# Central_Board.net
KiCad netlist of a schematic drawn in EAGLE
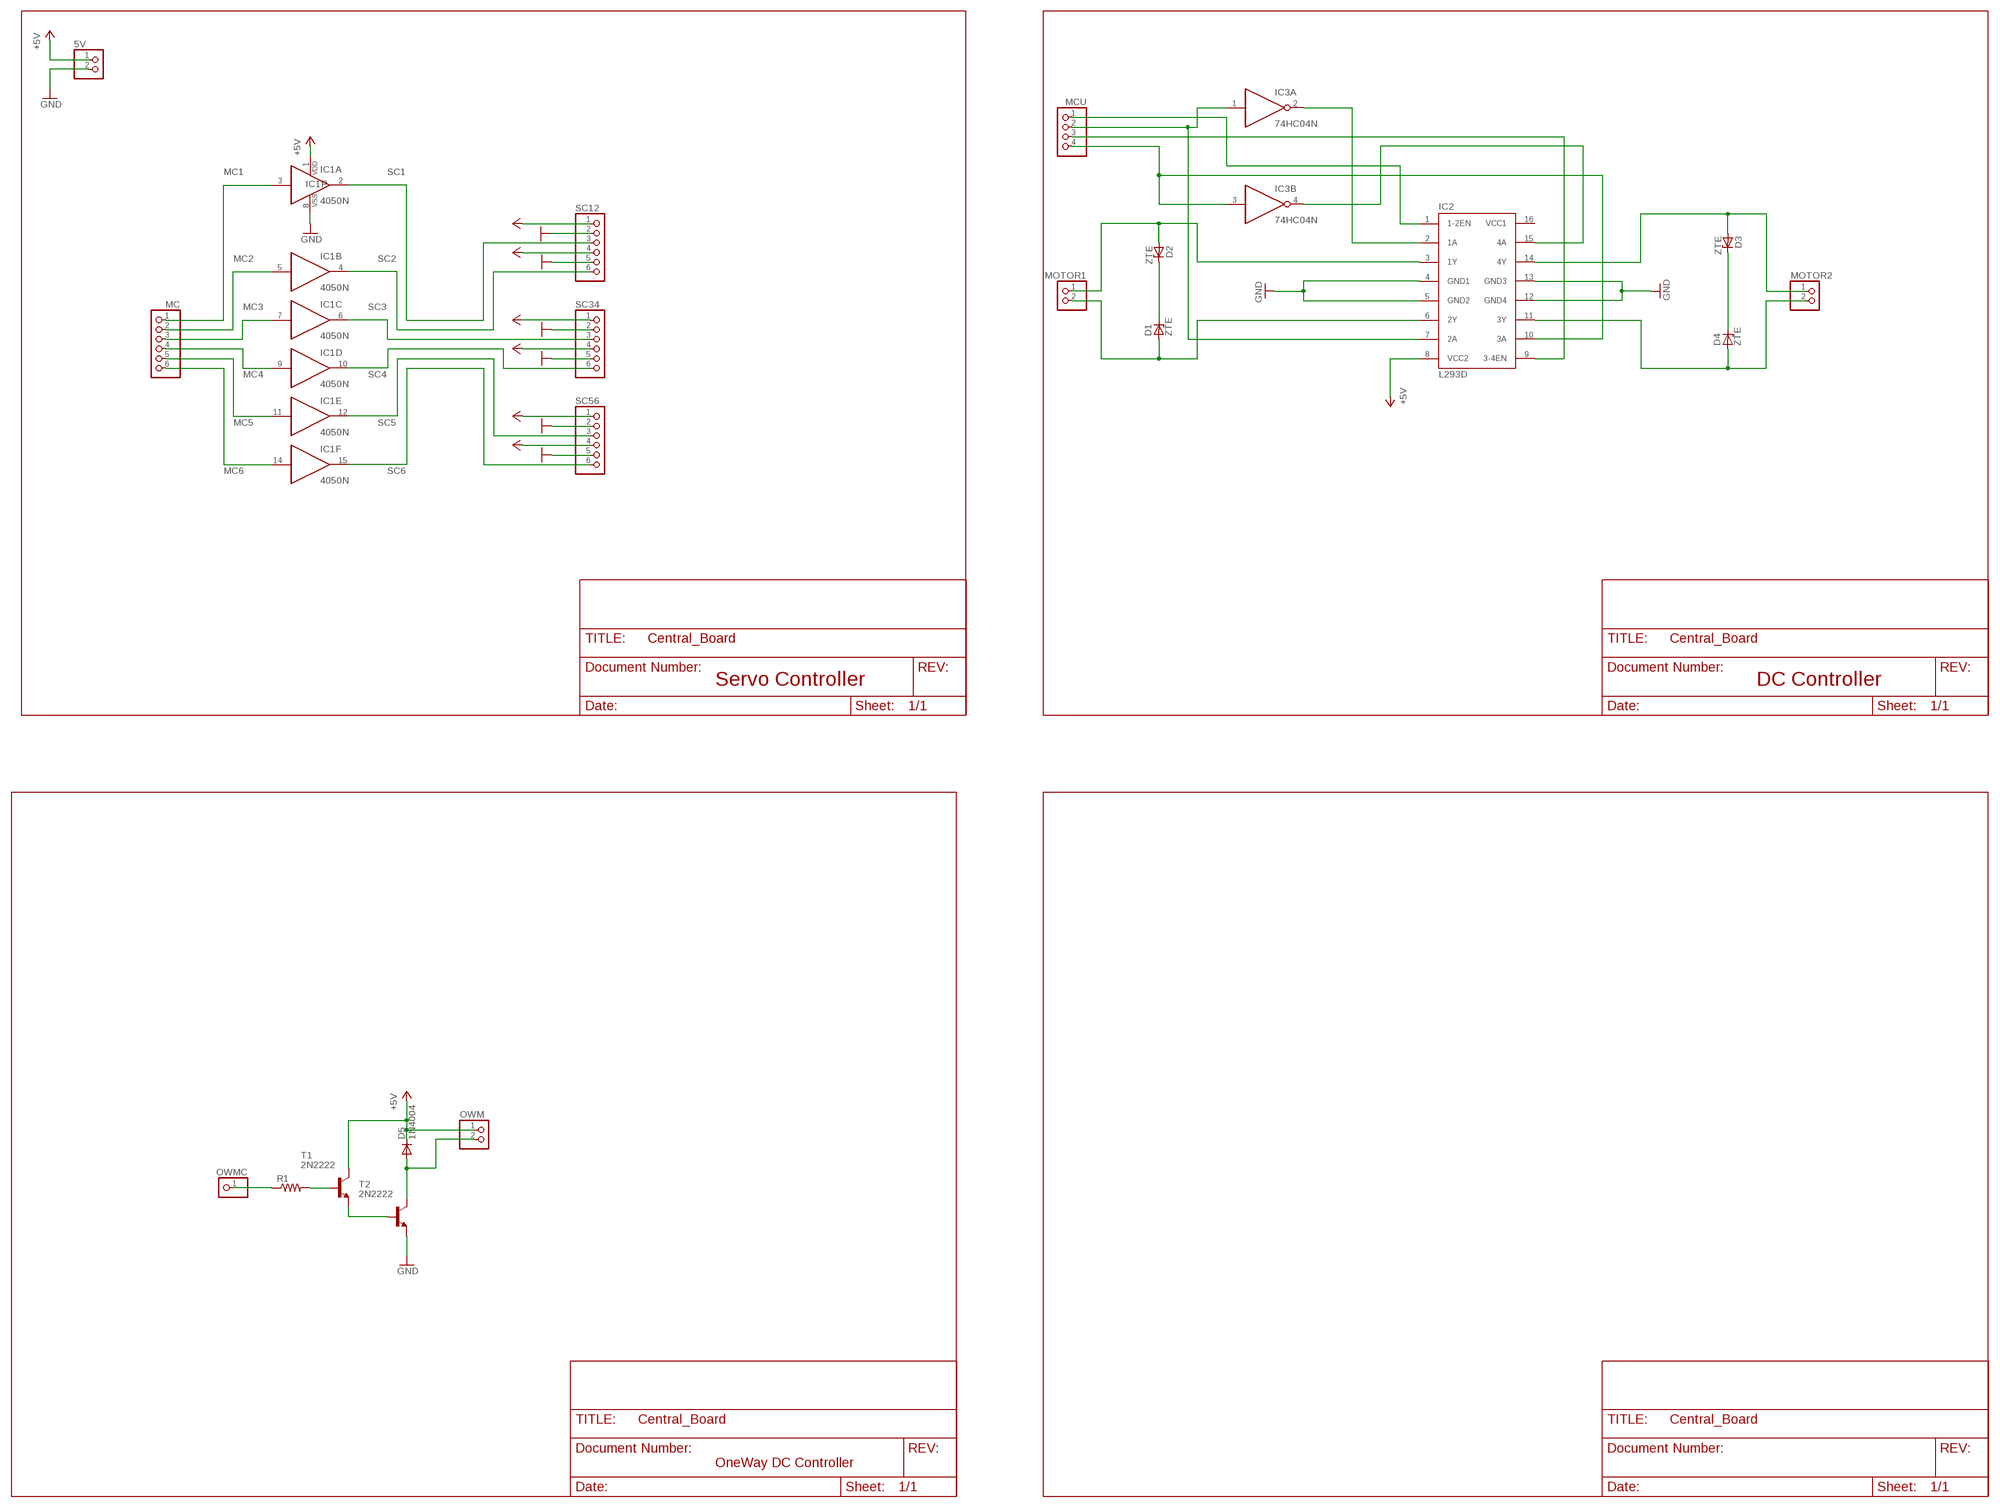
[diagram p0: schematic, sheet 1]

(export (version "E")
  (design (tool "Eeschema 10.0.6"))
  (components
    (comp (ref "5V")
      (value "PINHD-1X2")
      (footprint "eagle-import:1X02")
      (libsource (lib "eagle-import") (part "PINHD-1X2"))
    )
    (comp (ref "D1")
      (value "ZTE")
      (footprint "eagle-import:DO35Z10")
      (libsource (lib "eagle-import") (part "ZTE"))
    )
    (comp (ref "D2")
      (value "ZTE")
      (footprint "eagle-import:DO35Z10")
      (libsource (lib "eagle-import") (part "ZTE"))
    )
    (comp (ref "D3")
      (value "ZTE")
      (footprint "eagle-import:DO35Z10")
      (libsource (lib "eagle-import") (part "ZTE"))
    )
    (comp (ref "D4")
      (value "ZTE")
      (footprint "eagle-import:DO35Z10")
      (libsource (lib "eagle-import") (part "ZTE"))
    )
    (comp (ref "D5")
      (value "1N4004")
      (footprint "eagle-import:DO41-10")
      (libsource (lib "eagle-import") (part "1N4004"))
    )
    (comp (ref "IC1")
      (value "4050N")
      (footprint "eagle-import:DIL16")
      (libsource (lib "eagle-import") (part "4050N"))
    )
    (comp (ref "IC2")
      (value "L293D")
      (footprint "eagle-import:DIL16")
      (libsource (lib "eagle-import") (part "L293D"))
    )
    (comp (ref "IC3")
      (value "74HC04N")
      (footprint "eagle-import:DIL14")
      (libsource (lib "eagle-import") (part "7404NHC"))
    )
    (comp (ref "MC")
      (value "PINHD-1X6")
      (footprint "eagle-import:1X06")
      (libsource (lib "eagle-import") (part "PINHD-1X6"))
    )
    (comp (ref "MCU")
      (value "PINHD-1X4")
      (footprint "eagle-import:1X04")
      (libsource (lib "eagle-import") (part "PINHD-1X4"))
    )
    (comp (ref "MOTOR1")
      (value "PINHD-1X2")
      (footprint "eagle-import:1X02")
      (libsource (lib "eagle-import") (part "PINHD-1X2"))
    )
    (comp (ref "MOTOR2")
      (value "PINHD-1X2")
      (footprint "eagle-import:1X02")
      (libsource (lib "eagle-import") (part "PINHD-1X2"))
    )
    (comp (ref "OWM")
      (value "PINHD-1X2")
      (footprint "eagle-import:1X02")
      (libsource (lib "eagle-import") (part "PINHD-1X2"))
    )
    (comp (ref "OWMC")
      (value "PINHD-1X1")
      (footprint "eagle-import:1X01")
      (libsource (lib "eagle-import") (part "PINHD-1X1"))
    )
    (comp (ref "R1")
      (value "R-US_0207/10")
      (footprint "eagle-import:0207_10")
      (libsource (lib "eagle-import") (part "R-US_0207/10"))
    )
    (comp (ref "SC12")
      (value "PINHD-1X6")
      (footprint "eagle-import:1X06")
      (libsource (lib "eagle-import") (part "PINHD-1X6"))
    )
    (comp (ref "SC34")
      (value "PINHD-1X6")
      (footprint "eagle-import:1X06")
      (libsource (lib "eagle-import") (part "PINHD-1X6"))
    )
    (comp (ref "SC56")
      (value "PINHD-1X6")
      (footprint "eagle-import:1X06")
      (libsource (lib "eagle-import") (part "PINHD-1X6"))
    )
    (comp (ref "T1")
      (value "2N2222")
      (footprint "eagle-import:TO92-ECB")
      (libsource (lib "eagle-import") (part "-NPN-TO92-ECB"))
    )
    (comp (ref "T2")
      (value "2N2222")
      (footprint "eagle-import:TO92-ECB")
      (libsource (lib "eagle-import") (part "-NPN-TO92-ECB"))
    )
  )
  (nets
    (net (code "1") (name "+5V") (class "Default")
      (node (ref "5V") (pin "1") (pinfunction "1_1") (pintype "passive"))
      (node (ref "D5") (pin "C") (pinfunction "C_C") (pintype "passive"))
      (node (ref "IC1") (pin "1") (pinfunction "VDD_1") (pintype "power_in"))
      (node (ref "IC2") (pin "8") (pinfunction "VCC2_8") (pintype "power_in"))
      (node (ref "OWM") (pin "1") (pinfunction "1_1") (pintype "passive"))
      (node (ref "SC12") (pin "1") (pinfunction "1_1") (pintype "passive"))
      (node (ref "SC12") (pin "4") (pinfunction "4_4") (pintype "passive"))
      (node (ref "SC34") (pin "1") (pinfunction "1_1") (pintype "passive"))
      (node (ref "SC34") (pin "4") (pinfunction "4_4") (pintype "passive"))
      (node (ref "SC56") (pin "1") (pinfunction "1_1") (pintype "passive"))
      (node (ref "SC56") (pin "4") (pinfunction "4_4") (pintype "passive"))
      (node (ref "T1") (pin "C") (pinfunction "C_C") (pintype "passive"))
    )
    (net (code "2") (name "/MC1") (class "Default")
      (node (ref "IC1") (pin "3") (pinfunction "I_3") (pintype "input"))
      (node (ref "MC") (pin "1") (pinfunction "1_1") (pintype "passive"))
    )
    (net (code "3") (name "/MC2") (class "Default")
      (node (ref "IC1") (pin "5") (pinfunction "I_5") (pintype "input"))
      (node (ref "MC") (pin "2") (pinfunction "2_2") (pintype "passive"))
    )
    (net (code "4") (name "/MC3") (class "Default")
      (node (ref "IC1") (pin "7") (pinfunction "I_7") (pintype "input"))
      (node (ref "MC") (pin "3") (pinfunction "3_3") (pintype "passive"))
    )
    (net (code "5") (name "/MC4") (class "Default")
      (node (ref "IC1") (pin "9") (pinfunction "I_9") (pintype "input"))
      (node (ref "MC") (pin "4") (pinfunction "4_4") (pintype "passive"))
    )
    (net (code "6") (name "/MC5") (class "Default")
      (node (ref "IC1") (pin "11") (pinfunction "I_11") (pintype "input"))
      (node (ref "MC") (pin "5") (pinfunction "5_5") (pintype "passive"))
    )
    (net (code "7") (name "/MC6") (class "Default")
      (node (ref "IC1") (pin "14") (pinfunction "I_14") (pintype "input"))
      (node (ref "MC") (pin "6") (pinfunction "6_6") (pintype "passive"))
    )
    (net (code "8") (name "/SC1") (class "Default")
      (node (ref "IC1") (pin "2") (pinfunction "O_2") (pintype "output"))
      (node (ref "SC12") (pin "3") (pinfunction "3_3") (pintype "passive"))
    )
    (net (code "9") (name "/SC2") (class "Default")
      (node (ref "IC1") (pin "4") (pinfunction "O_4") (pintype "output"))
      (node (ref "SC12") (pin "6") (pinfunction "6_6") (pintype "passive"))
    )
    (net (code "10") (name "/SC3") (class "Default")
      (node (ref "IC1") (pin "6") (pinfunction "O_6") (pintype "output"))
      (node (ref "SC34") (pin "3") (pinfunction "3_3") (pintype "passive"))
    )
    (net (code "11") (name "/SC4") (class "Default")
      (node (ref "IC1") (pin "10") (pinfunction "O_10") (pintype "output"))
      (node (ref "SC34") (pin "6") (pinfunction "6_6") (pintype "passive"))
    )
    (net (code "12") (name "/SC5") (class "Default")
      (node (ref "IC1") (pin "12") (pinfunction "O_12") (pintype "output"))
      (node (ref "SC56") (pin "3") (pinfunction "3_3") (pintype "passive"))
    )
    (net (code "13") (name "/SC6") (class "Default")
      (node (ref "IC1") (pin "15") (pinfunction "O_15") (pintype "output"))
      (node (ref "SC56") (pin "6") (pinfunction "6_6") (pintype "passive"))
    )
    (net (code "14") (name "/VCC1") (class "Default")
      (node (ref "IC2") (pin "16") (pinfunction "VCC1_16") (pintype "power_in"))
    )
    (net (code "15") (name "GND") (class "Default")
      (node (ref "5V") (pin "2") (pinfunction "2_2") (pintype "passive"))
      (node (ref "IC1") (pin "8") (pinfunction "VSS_8") (pintype "power_in"))
      (node (ref "IC2") (pin "12") (pinfunction "GND4_12") (pintype "power_in"))
      (node (ref "IC2") (pin "13") (pinfunction "GND3_13") (pintype "power_in"))
      (node (ref "IC2") (pin "4") (pinfunction "GND1_4") (pintype "power_in"))
      (node (ref "IC2") (pin "5") (pinfunction "GND2_5") (pintype "power_in"))
      (node (ref "SC12") (pin "2") (pinfunction "2_2") (pintype "passive"))
      (node (ref "SC12") (pin "5") (pinfunction "5_5") (pintype "passive"))
      (node (ref "SC34") (pin "2") (pinfunction "2_2") (pintype "passive"))
      (node (ref "SC34") (pin "5") (pinfunction "5_5") (pintype "passive"))
      (node (ref "SC56") (pin "2") (pinfunction "2_2") (pintype "passive"))
      (node (ref "SC56") (pin "5") (pinfunction "5_5") (pintype "passive"))
      (node (ref "T2") (pin "E") (pinfunction "E_E") (pintype "passive"))
    )
    (net (code "16") (name "Net-(D1-PadC)") (class "Default")
      (node (ref "D1") (pin "C") (pinfunction "C_C") (pintype "passive"))
      (node (ref "D2") (pin "C") (pinfunction "C_C") (pintype "passive"))
    )
    (net (code "17") (name "Net-(D3-PadC)") (class "Default")
      (node (ref "D3") (pin "C") (pinfunction "C_C") (pintype "passive"))
      (node (ref "D4") (pin "C") (pinfunction "C_C") (pintype "passive"))
    )
    (net (code "18") (name "Net-(D5-PadA)") (class "Default")
      (node (ref "D5") (pin "A") (pinfunction "A_A") (pintype "passive"))
      (node (ref "OWM") (pin "2") (pinfunction "2_2") (pintype "passive"))
      (node (ref "T2") (pin "C") (pinfunction "C_C") (pintype "passive"))
    )
    (net (code "19") (name "Net-(IC2-1-2EN)") (class "Default")
      (node (ref "IC2") (pin "1") (pinfunction "1-2EN_1") (pintype "input"))
      (node (ref "MCU") (pin "1") (pinfunction "1_1") (pintype "passive"))
    )
    (net (code "20") (name "Net-(IC2-1A)") (class "Default")
      (node (ref "IC2") (pin "2") (pinfunction "1A_2") (pintype "input"))
      (node (ref "IC3") (pin "2") (pinfunction "O_2") (pintype "output"))
    )
    (net (code "21") (name "Net-(IC2-1Y)") (class "Default")
      (node (ref "D2") (pin "A") (pinfunction "A_A") (pintype "passive"))
      (node (ref "IC2") (pin "3") (pinfunction "1Y_3") (pintype "output"))
      (node (ref "MOTOR1") (pin "1") (pinfunction "1_1") (pintype "passive"))
    )
    (net (code "22") (name "Net-(IC2-2A)") (class "Default")
      (node (ref "IC2") (pin "7") (pinfunction "2A_7") (pintype "input"))
      (node (ref "IC3") (pin "1") (pinfunction "I_1") (pintype "input"))
      (node (ref "MCU") (pin "2") (pinfunction "2_2") (pintype "passive"))
    )
    (net (code "23") (name "Net-(IC2-2Y)") (class "Default")
      (node (ref "D1") (pin "A") (pinfunction "A_A") (pintype "passive"))
      (node (ref "IC2") (pin "6") (pinfunction "2Y_6") (pintype "output"))
      (node (ref "MOTOR1") (pin "2") (pinfunction "2_2") (pintype "passive"))
    )
    (net (code "24") (name "Net-(IC2-3-4EN)") (class "Default")
      (node (ref "IC2") (pin "9") (pinfunction "3-4EN_9") (pintype "input"))
      (node (ref "MCU") (pin "3") (pinfunction "3_3") (pintype "passive"))
    )
    (net (code "25") (name "Net-(IC2-3A)") (class "Default")
      (node (ref "IC2") (pin "10") (pinfunction "3A_10") (pintype "input"))
      (node (ref "IC3") (pin "3") (pinfunction "I_3") (pintype "input"))
      (node (ref "MCU") (pin "4") (pinfunction "4_4") (pintype "passive"))
    )
    (net (code "26") (name "Net-(IC2-3Y)") (class "Default")
      (node (ref "D4") (pin "A") (pinfunction "A_A") (pintype "passive"))
      (node (ref "IC2") (pin "11") (pinfunction "3Y_11") (pintype "output"))
      (node (ref "MOTOR2") (pin "2") (pinfunction "2_2") (pintype "passive"))
    )
    (net (code "27") (name "Net-(IC2-4A)") (class "Default")
      (node (ref "IC2") (pin "15") (pinfunction "4A_15") (pintype "input"))
      (node (ref "IC3") (pin "4") (pinfunction "O_4") (pintype "output"))
    )
    (net (code "28") (name "Net-(IC2-4Y)") (class "Default")
      (node (ref "D3") (pin "A") (pinfunction "A_A") (pintype "passive"))
      (node (ref "IC2") (pin "14") (pinfunction "4Y_14") (pintype "output"))
      (node (ref "MOTOR2") (pin "1") (pinfunction "1_1") (pintype "passive"))
    )
    (net (code "29") (name "Net-(OWMC-Pad1)") (class "Default")
      (node (ref "OWMC") (pin "1") (pinfunction "1_1") (pintype "passive"))
      (node (ref "R1") (pin "1") (pinfunction "1_1") (pintype "passive"))
    )
    (net (code "30") (name "Net-(R1-Pad2)") (class "Default")
      (node (ref "R1") (pin "2") (pinfunction "2_2") (pintype "passive"))
      (node (ref "T1") (pin "B") (pinfunction "B_B") (pintype "passive"))
    )
    (net (code "31") (name "Net-(T1-PadE)") (class "Default")
      (node (ref "T1") (pin "E") (pinfunction "E_E") (pintype "passive"))
      (node (ref "T2") (pin "B") (pinfunction "B_B") (pintype "passive"))
    )
  )
)
